# Sheet1.net
KiCad netlist of a schematic drawn in Altium Designer
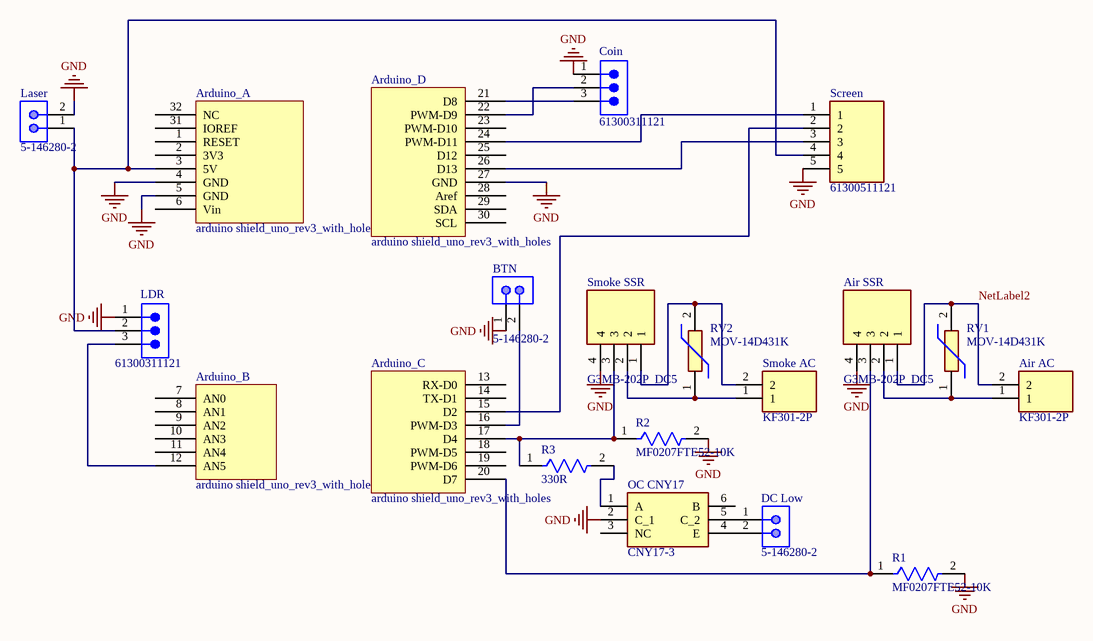
[diagram p0: Sheet1.SchDoc]

(export (version "E")
  (design (tool "Eeschema 10.0.6"))
  (components
    (comp (ref "Air AC")
      (value "KF301-2P")
      (footprint "SamacSys:KF3012P")
      (description "Connector")
      (libsource (lib "*") (part "KF301-2P"))
    )
    (comp (ref "Air SSR")
      (value "G3MB-202P_DC5")
      (footprint "SamacSys:G3MC-201PL")
      (description "Relay or Contactor")
      (fields
        (field (name "MANUFACTURER_PART_NUMBER") "G3MB-202P DC5")
        (field (name "MOUSER PART NUMBER") "653-G3MB-202P-DC5")
      )
      (libsource (lib "*") (part "G3MB-202P_DC5"))
    )
    (comp (ref "Arduino_")
      (value "arduino shield_uno_rev3_with_holes")
      (footprint "ARDUINO UNO SHIELD WITH 3D MODEL")
      (libsource (lib "PCB_Kursus_Library") (part "arduino shield_uno_rev3_with_holes"))
    )
    (comp (ref "BTN")
      (value "5-146280-2")
      (footprint "TECO-5-146280-2_V")
      (fields (field (name "MANUFACTURER") "TE Connectivity"))
      (libsource (lib "Altium Content Vault") (part "CN-1P-M-R2"))
    )
    (comp (ref "Coin")
      (value "61300311121")
      (footprint "61300311121")
      (libsource (lib "Altium Content Vault") (part "Header_Male_1R_03P"))
    )
    (comp (ref "DC Low")
      (value "5-146280-2")
      (footprint "TECO-5-146280-2_V")
      (fields (field (name "MANUFACTURER") "TE Connectivity"))
      (libsource (lib "") (part "CN-1P-M-R2_2"))
    )
    (comp (ref "Laser")
      (value "5-146280-2")
      (footprint "TECO-5-146280-2_V")
      (fields (field (name "MANUFACTURER") "TE Connectivity"))
      (libsource (lib "") (part "CN-1P-M-R2_1"))
    )
    (comp (ref "LDR")
      (value "61300311121")
      (footprint "61300311121")
      (libsource (lib "Altium Content Vault") (part "Header_Male_1R_03P"))
    )
    (comp (ref "OC CNY17")
      (value "CNY17-3")
      (footprint "SamacSys:DIP762W60P254L730H430Q6N")
      (description "Transistor")
      (fields (field (name "MOUSER PART NUMBER") "782-CNY17-3"))
      (libsource (lib "*") (part "CNY17-3"))
    )
    (comp (ref "R1")
      (value "MF0207FTE52-10K")
      (footprint "FP-MF0207-MFG")
      (description "RES 10K OHM 1% 0.6W AXIAL")
      (fields (field (name "TOLERANCE") "1%"))
      (libsource (lib "Altium Content Vault") (part "1029c3af85768c4190bb7ad29bc67b5"))
    )
    (comp (ref "R2")
      (value "MF0207FTE52-10K")
      (footprint "FP-MF0207-MFG")
      (description "RES 10K OHM 1% 0.6W AXIAL")
      (fields (field (name "TOLERANCE") "1%"))
      (libsource (lib "Altium Content Vault") (part "1029c3af85768c4190bb7ad29bc67b5"))
    )
    (comp (ref "R3")
      (value "330R")
      (footprint "FP-MF0207-MFG")
      (description "RES 330 OHM AXIAL")
      (fields (field (name "TOLERANCE") "1%"))
      (libsource (lib "Altium Content Vault") (part "1029c3af85768c4190bb7ad29bc67b5"))
    )
    (comp (ref "RV1")
      (value "MOV-14D431K")
      (footprint "SamacSys:MOV-14D(5.2MM-T)")
      (description "Varistor")
      (fields (field (name "MOUSER PART NUMBER") "652-MOV-14D431K"))
      (libsource (lib "*") (part "MOV-14D431K"))
    )
    (comp (ref "RV2")
      (value "MOV-14D431K")
      (footprint "SamacSys:MOV-14D(5.2MM-T)")
      (description "Varistor")
      (fields (field (name "MOUSER PART NUMBER") "652-MOV-14D431K"))
      (libsource (lib "*") (part "MOV-14D431K"))
    )
    (comp (ref "Screen")
      (value "61300511121")
      (footprint "SamacSys:HDRV5W64P0X254_1X5_1270X254X854P")
      (description "Connector")
      (fields (field (name "MOUSER PART NUMBER") "710-61300511121"))
      (libsource (lib "*") (part "61300511121"))
    )
    (comp (ref "Smoke AC")
      (value "KF301-2P")
      (footprint "SamacSys:KF3012P")
      (description "Connector")
      (libsource (lib "*") (part "KF301-2P"))
    )
    (comp (ref "Smoke SSR")
      (value "G3MB-202P_DC5")
      (footprint "SamacSys:G3MC-201PL")
      (description "Relay or Contactor")
      (fields
        (field (name "MANUFACTURER_PART_NUMBER") "G3MB-202P DC5")
        (field (name "MOUSER PART NUMBER") "653-G3MB-202P-DC5")
      )
      (libsource (lib "*") (part "G3MB-202P_DC5"))
    )
  )
  (nets
    (net (code "1") (name "/NetLabel2") (class "Default")
      (node (ref "Air AC") (pin "2") (pinfunction "2_2") (pintype "passive"))
      (node (ref "Air SSR") (pin "1") (pinfunction "1_1") (pintype "passive"))
      (node (ref "RV1") (pin "2") (pinfunction "2_2") (pintype "passive"))
    )
    (net (code "2") (name "GND") (class "Default")
      (node (ref "Air SSR") (pin "4") (pinfunction "4_4") (pintype "passive"))
      (node (ref "Arduino_") (pin "27") (pinfunction "GND_27") (pintype "passive"))
      (node (ref "Arduino_") (pin "4") (pinfunction "GND_4") (pintype "passive"))
      (node (ref "Arduino_") (pin "5") (pinfunction "GND_5") (pintype "passive"))
      (node (ref "BTN") (pin "1") (pinfunction "1_1") (pintype "passive"))
      (node (ref "Coin") (pin "1") (pinfunction "1_1") (pintype "passive"))
      (node (ref "LDR") (pin "1") (pinfunction "1_1") (pintype "passive"))
      (node (ref "Laser") (pin "2") (pinfunction "2_2") (pintype "passive"))
      (node (ref "OC CNY17") (pin "2") (pinfunction "C_1_2") (pintype "passive"))
      (node (ref "R1") (pin "2") (pinfunction "2_2") (pintype "passive"))
      (node (ref "R2") (pin "2") (pinfunction "2_2") (pintype "passive"))
      (node (ref "Screen") (pin "5") (pinfunction "5_5") (pintype "passive"))
      (node (ref "Smoke SSR") (pin "4") (pinfunction "4_4") (pintype "passive"))
    )
    (net (code "3") (name "Net-(Air AC-Pad1)") (class "Default")
      (node (ref "Air AC") (pin "1") (pinfunction "1_1") (pintype "passive"))
      (node (ref "Air SSR") (pin "2") (pinfunction "2_2") (pintype "passive"))
      (node (ref "RV1") (pin "1") (pinfunction "1_1") (pintype "passive"))
    )
    (net (code "4") (name "Net-(Arduino_A-5V)") (class "Default")
      (node (ref "Arduino_") (pin "3") (pinfunction "5V_3") (pintype "passive"))
      (node (ref "LDR") (pin "2") (pinfunction "2_2") (pintype "passive"))
      (node (ref "Laser") (pin "1") (pinfunction "1_1") (pintype "passive"))
      (node (ref "Screen") (pin "4") (pinfunction "4_4") (pintype "passive"))
    )
    (net (code "5") (name "Net-(Arduino_B-AN5)") (class "Default")
      (node (ref "Arduino_") (pin "12") (pinfunction "AN5_12") (pintype "passive"))
      (node (ref "LDR") (pin "3") (pinfunction "3_3") (pintype "passive"))
    )
    (net (code "6") (name "Net-(Arduino_C-D2)") (class "Default")
      (node (ref "Arduino_") (pin "15") (pinfunction "D2_15") (pintype "passive"))
      (node (ref "Screen") (pin "2") (pinfunction "2_2") (pintype "passive"))
    )
    (net (code "7") (name "Net-(Arduino_C-D4)") (class "Default")
      (node (ref "Arduino_") (pin "17") (pinfunction "D4_17") (pintype "passive"))
      (node (ref "R2") (pin "1") (pinfunction "1_1") (pintype "passive"))
      (node (ref "R3") (pin "1") (pinfunction "1_1") (pintype "passive"))
      (node (ref "Smoke SSR") (pin "3") (pinfunction "3_3") (pintype "passive"))
    )
    (net (code "8") (name "Net-(Arduino_C-D7)") (class "Default")
      (node (ref "Air SSR") (pin "3") (pinfunction "3_3") (pintype "passive"))
      (node (ref "Arduino_") (pin "20") (pinfunction "D7_20") (pintype "passive"))
      (node (ref "R1") (pin "1") (pinfunction "1_1") (pintype "passive"))
    )
    (net (code "9") (name "Net-(Arduino_C-PWM-D3)") (class "Default")
      (node (ref "Arduino_") (pin "16") (pinfunction "PWM-D3_16") (pintype "passive"))
      (node (ref "BTN") (pin "2") (pinfunction "2_2") (pintype "passive"))
    )
    (net (code "10") (name "Net-(Arduino_D-D8)") (class "Default")
      (node (ref "Arduino_") (pin "21") (pinfunction "D8_21") (pintype "passive"))
      (node (ref "Coin") (pin "3") (pinfunction "3_3") (pintype "passive"))
    )
    (net (code "11") (name "Net-(Arduino_D-D13)") (class "Default")
      (node (ref "Arduino_") (pin "26") (pinfunction "D13_26") (pintype "passive"))
      (node (ref "Screen") (pin "3") (pinfunction "3_3") (pintype "passive"))
    )
    (net (code "12") (name "Net-(Arduino_D-PWM-D9)") (class "Default")
      (node (ref "Arduino_") (pin "22") (pinfunction "PWM-D9_22") (pintype "passive"))
      (node (ref "Coin") (pin "2") (pinfunction "2_2") (pintype "passive"))
    )
    (net (code "13") (name "Net-(Arduino_D-PWM-D11)") (class "Default")
      (node (ref "Arduino_") (pin "24") (pinfunction "PWM-D11_24") (pintype "passive"))
      (node (ref "Screen") (pin "1") (pinfunction "1_1") (pintype "passive"))
    )
    (net (code "14") (name "Net-(OC CNY17-A)") (class "Default")
      (node (ref "OC CNY17") (pin "1") (pinfunction "A_1") (pintype "passive"))
      (node (ref "R3") (pin "2") (pinfunction "2_2") (pintype "passive"))
    )
    (net (code "15") (name "Net-(OC CNY17-C_2)") (class "Default")
      (node (ref "DC Low") (pin "1") (pinfunction "1_1") (pintype "passive"))
      (node (ref "OC CNY17") (pin "5") (pinfunction "C_2_5") (pintype "passive"))
    )
    (net (code "16") (name "Net-(OC CNY17-E)") (class "Default")
      (node (ref "DC Low") (pin "2") (pinfunction "2_2") (pintype "passive"))
      (node (ref "OC CNY17") (pin "4") (pinfunction "E_4") (pintype "passive"))
    )
    (net (code "17") (name "Net-(RV2-Pad1)") (class "Default")
      (node (ref "RV2") (pin "1") (pinfunction "1_1") (pintype "passive"))
      (node (ref "Smoke AC") (pin "1") (pinfunction "1_1") (pintype "passive"))
      (node (ref "Smoke SSR") (pin "2") (pinfunction "2_2") (pintype "passive"))
    )
    (net (code "18") (name "Net-(RV2-Pad2)") (class "Default")
      (node (ref "RV2") (pin "2") (pinfunction "2_2") (pintype "passive"))
      (node (ref "Smoke AC") (pin "2") (pinfunction "2_2") (pintype "passive"))
      (node (ref "Smoke SSR") (pin "1") (pinfunction "1_1") (pintype "passive"))
    )
    (net (code "19") (name "unconnected-(Arduino_A-3V3-Pad2)") (class "Default")
      (node (ref "Arduino_") (pin "2") (pinfunction "3V3_2") (pintype "passive"))
    )
    (net (code "20") (name "unconnected-(Arduino_A-IOREF-Pad31)") (class "Default")
      (node (ref "Arduino_") (pin "31") (pinfunction "IOREF_31") (pintype "passive"))
    )
    (net (code "21") (name "unconnected-(Arduino_A-NC-Pad32)") (class "Default")
      (node (ref "Arduino_") (pin "32") (pinfunction "NC_32") (pintype "passive"))
    )
    (net (code "22") (name "unconnected-(Arduino_A-RESET-Pad1)") (class "Default")
      (node (ref "Arduino_") (pin "1") (pinfunction "RESET_1") (pintype "passive"))
    )
    (net (code "23") (name "unconnected-(Arduino_A-Vin-Pad6)") (class "Default")
      (node (ref "Arduino_") (pin "6") (pinfunction "Vin_6") (pintype "passive"))
    )
    (net (code "24") (name "unconnected-(Arduino_B-AN0-Pad7)") (class "Default")
      (node (ref "Arduino_") (pin "7") (pinfunction "AN0_7") (pintype "passive"))
    )
    (net (code "25") (name "unconnected-(Arduino_B-AN1-Pad8)") (class "Default")
      (node (ref "Arduino_") (pin "8") (pinfunction "AN1_8") (pintype "passive"))
    )
    (net (code "26") (name "unconnected-(Arduino_B-AN2-Pad9)") (class "Default")
      (node (ref "Arduino_") (pin "9") (pinfunction "AN2_9") (pintype "passive"))
    )
    (net (code "27") (name "unconnected-(Arduino_B-AN3-Pad10)") (class "Default")
      (node (ref "Arduino_") (pin "10") (pinfunction "AN3_10") (pintype "passive"))
    )
    (net (code "28") (name "unconnected-(Arduino_B-AN4-Pad11)") (class "Default")
      (node (ref "Arduino_") (pin "11") (pinfunction "AN4_11") (pintype "passive"))
    )
    (net (code "29") (name "unconnected-(Arduino_C-PWM-D5-Pad18)") (class "Default")
      (node (ref "Arduino_") (pin "18") (pinfunction "PWM-D5_18") (pintype "passive"))
    )
    (net (code "30") (name "unconnected-(Arduino_C-PWM-D6-Pad19)") (class "Default")
      (node (ref "Arduino_") (pin "19") (pinfunction "PWM-D6_19") (pintype "passive"))
    )
    (net (code "31") (name "unconnected-(Arduino_C-RX-D0-Pad13)") (class "Default")
      (node (ref "Arduino_") (pin "13") (pinfunction "RX-D0_13") (pintype "passive"))
    )
    (net (code "32") (name "unconnected-(Arduino_C-TX-D1-Pad14)") (class "Default")
      (node (ref "Arduino_") (pin "14") (pinfunction "TX-D1_14") (pintype "passive"))
    )
    (net (code "33") (name "unconnected-(Arduino_D-Aref-Pad28)") (class "Default")
      (node (ref "Arduino_") (pin "28") (pinfunction "Aref_28") (pintype "passive"))
    )
    (net (code "34") (name "unconnected-(Arduino_D-D12-Pad25)") (class "Default")
      (node (ref "Arduino_") (pin "25") (pinfunction "D12_25") (pintype "passive"))
    )
    (net (code "35") (name "unconnected-(Arduino_D-PWM-D10-Pad23)") (class "Default")
      (node (ref "Arduino_") (pin "23") (pinfunction "PWM-D10_23") (pintype "passive"))
    )
    (net (code "36") (name "unconnected-(Arduino_D-SCL-Pad30)") (class "Default")
      (node (ref "Arduino_") (pin "30") (pinfunction "SCL_30") (pintype "passive"))
    )
    (net (code "37") (name "unconnected-(Arduino_D-SDA-Pad29)") (class "Default")
      (node (ref "Arduino_") (pin "29") (pinfunction "SDA_29") (pintype "passive"))
    )
    (net (code "38") (name "unconnected-(OC CNY17-B-Pad6)") (class "Default")
      (node (ref "OC CNY17") (pin "6") (pinfunction "B_6") (pintype "passive"))
    )
    (net (code "39") (name "unconnected-(OC CNY17-NC-Pad3)") (class "Default")
      (node (ref "OC CNY17") (pin "3") (pinfunction "NC_3") (pintype "passive"))
    )
  )
)
